# board.net
KiCad netlist of a schematic drawn in EAGLE
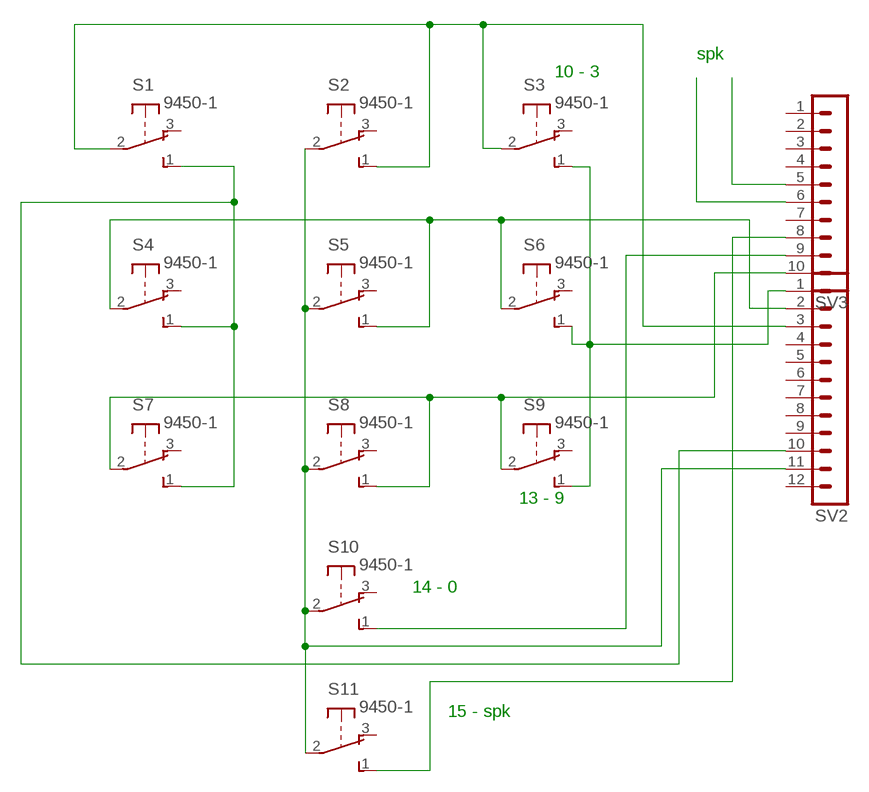
[diagram p0: schematic, sheet 1]

(export (version "E")
  (design (tool "Eeschema 10.0.6"))
  (components
    (comp (ref "S1")
      (value "9450-1")
      (footprint "eagle-import:9450-1")
      (libsource (lib "eagle-import") (part "9450-1"))
    )
    (comp (ref "S2")
      (value "9450-1")
      (footprint "eagle-import:9450-1")
      (libsource (lib "eagle-import") (part "9450-1"))
    )
    (comp (ref "S3")
      (value "9450-1")
      (footprint "eagle-import:9450-1")
      (libsource (lib "eagle-import") (part "9450-1"))
    )
    (comp (ref "S4")
      (value "9450-1")
      (footprint "eagle-import:9450-1")
      (libsource (lib "eagle-import") (part "9450-1"))
    )
    (comp (ref "S5")
      (value "9450-1")
      (footprint "eagle-import:9450-1")
      (libsource (lib "eagle-import") (part "9450-1"))
    )
    (comp (ref "S6")
      (value "9450-1")
      (footprint "eagle-import:9450-1")
      (libsource (lib "eagle-import") (part "9450-1"))
    )
    (comp (ref "S7")
      (value "9450-1")
      (footprint "eagle-import:9450-1")
      (libsource (lib "eagle-import") (part "9450-1"))
    )
    (comp (ref "S8")
      (value "9450-1")
      (footprint "eagle-import:9450-1")
      (libsource (lib "eagle-import") (part "9450-1"))
    )
    (comp (ref "S9")
      (value "9450-1")
      (footprint "eagle-import:9450-1")
      (libsource (lib "eagle-import") (part "9450-1"))
    )
    (comp (ref "S10")
      (value "9450-1")
      (footprint "eagle-import:9450-1")
      (libsource (lib "eagle-import") (part "9450-1"))
    )
    (comp (ref "S11")
      (value "9450-1")
      (footprint "eagle-import:9450-1")
      (libsource (lib "eagle-import") (part "9450-1"))
    )
    (comp (ref "SV2")
      (value "MA12-1")
      (footprint "eagle-import:MA12-1")
      (libsource (lib "eagle-import") (part "MA12-1"))
    )
    (comp (ref "SV3")
      (value "MA10-1")
      (footprint "eagle-import:MA10-1")
      (libsource (lib "eagle-import") (part "MA10-1"))
    )
  )
  (nets
    (net (code "1") (name "Net-(S1-P)") (class "Default")
      (node (ref "S1") (pin "2") (pinfunction "P_2") (pintype "passive"))
      (node (ref "S2") (pin "1") (pinfunction "S_1") (pintype "passive"))
      (node (ref "S3") (pin "2") (pinfunction "P_2") (pintype "passive"))
      (node (ref "SV2") (pin "3") (pinfunction "3_3") (pintype "passive"))
    )
    (net (code "2") (name "Net-(S1-S)") (class "Default")
      (node (ref "S1") (pin "1") (pinfunction "S_1") (pintype "passive"))
      (node (ref "S4") (pin "1") (pinfunction "S_1") (pintype "passive"))
      (node (ref "S7") (pin "1") (pinfunction "S_1") (pintype "passive"))
      (node (ref "SV2") (pin "10") (pinfunction "10_10") (pintype "passive"))
    )
    (net (code "3") (name "Net-(S3-S)") (class "Default")
      (node (ref "S3") (pin "1") (pinfunction "S_1") (pintype "passive"))
      (node (ref "S6") (pin "1") (pinfunction "S_1") (pintype "passive"))
      (node (ref "S9") (pin "1") (pinfunction "S_1") (pintype "passive"))
      (node (ref "SV2") (pin "1") (pinfunction "1_1") (pintype "passive"))
    )
    (net (code "4") (name "Net-(S4-P)") (class "Default")
      (node (ref "S4") (pin "2") (pinfunction "P_2") (pintype "passive"))
      (node (ref "S5") (pin "1") (pinfunction "S_1") (pintype "passive"))
      (node (ref "S6") (pin "2") (pinfunction "P_2") (pintype "passive"))
      (node (ref "SV2") (pin "2") (pinfunction "2_2") (pintype "passive"))
    )
    (net (code "5") (name "Net-(S7-P)") (class "Default")
      (node (ref "S7") (pin "2") (pinfunction "P_2") (pintype "passive"))
      (node (ref "S8") (pin "1") (pinfunction "S_1") (pintype "passive"))
      (node (ref "S9") (pin "2") (pinfunction "P_2") (pintype "passive"))
      (node (ref "SV3") (pin "10") (pinfunction "10_10") (pintype "passive"))
    )
    (net (code "6") (name "Net-(S10-P)") (class "Default")
      (node (ref "S10") (pin "2") (pinfunction "P_2") (pintype "passive"))
      (node (ref "S11") (pin "2") (pinfunction "P_2") (pintype "passive"))
      (node (ref "S2") (pin "2") (pinfunction "P_2") (pintype "passive"))
      (node (ref "S5") (pin "2") (pinfunction "P_2") (pintype "passive"))
      (node (ref "S8") (pin "2") (pinfunction "P_2") (pintype "passive"))
      (node (ref "SV2") (pin "11") (pinfunction "11_11") (pintype "passive"))
    )
    (net (code "7") (name "Net-(S10-S)") (class "Default")
      (node (ref "S10") (pin "1") (pinfunction "S_1") (pintype "passive"))
      (node (ref "SV3") (pin "9") (pinfunction "9_9") (pintype "passive"))
    )
    (net (code "8") (name "Net-(S11-S)") (class "Default")
      (node (ref "S11") (pin "1") (pinfunction "S_1") (pintype "passive"))
      (node (ref "SV3") (pin "8") (pinfunction "8_8") (pintype "passive"))
    )
    (net (code "9") (name "unconnected-(S1-O-Pad3)") (class "Default")
      (node (ref "S1") (pin "3") (pinfunction "O_3") (pintype "passive"))
    )
    (net (code "10") (name "unconnected-(S2-O-Pad3)") (class "Default")
      (node (ref "S2") (pin "3") (pinfunction "O_3") (pintype "passive"))
    )
    (net (code "11") (name "unconnected-(S3-O-Pad3)") (class "Default")
      (node (ref "S3") (pin "3") (pinfunction "O_3") (pintype "passive"))
    )
    (net (code "12") (name "unconnected-(S4-O-Pad3)") (class "Default")
      (node (ref "S4") (pin "3") (pinfunction "O_3") (pintype "passive"))
    )
    (net (code "13") (name "unconnected-(S5-O-Pad3)") (class "Default")
      (node (ref "S5") (pin "3") (pinfunction "O_3") (pintype "passive"))
    )
    (net (code "14") (name "unconnected-(S6-O-Pad3)") (class "Default")
      (node (ref "S6") (pin "3") (pinfunction "O_3") (pintype "passive"))
    )
    (net (code "15") (name "unconnected-(S7-O-Pad3)") (class "Default")
      (node (ref "S7") (pin "3") (pinfunction "O_3") (pintype "passive"))
    )
    (net (code "16") (name "unconnected-(S8-O-Pad3)") (class "Default")
      (node (ref "S8") (pin "3") (pinfunction "O_3") (pintype "passive"))
    )
    (net (code "17") (name "unconnected-(S9-O-Pad3)") (class "Default")
      (node (ref "S9") (pin "3") (pinfunction "O_3") (pintype "passive"))
    )
    (net (code "18") (name "unconnected-(S10-O-Pad3)") (class "Default")
      (node (ref "S10") (pin "3") (pinfunction "O_3") (pintype "passive"))
    )
    (net (code "19") (name "unconnected-(S11-O-Pad3)") (class "Default")
      (node (ref "S11") (pin "3") (pinfunction "O_3") (pintype "passive"))
    )
    (net (code "20") (name "unconnected-(SV2-Pad4)") (class "Default")
      (node (ref "SV2") (pin "4") (pinfunction "4_4") (pintype "passive"))
    )
    (net (code "21") (name "unconnected-(SV2-Pad5)") (class "Default")
      (node (ref "SV2") (pin "5") (pinfunction "5_5") (pintype "passive"))
    )
    (net (code "22") (name "unconnected-(SV2-Pad6)") (class "Default")
      (node (ref "SV2") (pin "6") (pinfunction "6_6") (pintype "passive"))
    )
    (net (code "23") (name "unconnected-(SV2-Pad7)") (class "Default")
      (node (ref "SV2") (pin "7") (pinfunction "7_7") (pintype "passive"))
    )
    (net (code "24") (name "unconnected-(SV2-Pad8)") (class "Default")
      (node (ref "SV2") (pin "8") (pinfunction "8_8") (pintype "passive"))
    )
    (net (code "25") (name "unconnected-(SV2-Pad9)") (class "Default")
      (node (ref "SV2") (pin "9") (pinfunction "9_9") (pintype "passive"))
    )
    (net (code "26") (name "unconnected-(SV2-Pad12)") (class "Default")
      (node (ref "SV2") (pin "12") (pinfunction "12_12") (pintype "passive"))
    )
    (net (code "27") (name "unconnected-(SV3-Pad1)") (class "Default")
      (node (ref "SV3") (pin "1") (pinfunction "1_1") (pintype "passive"))
    )
    (net (code "28") (name "unconnected-(SV3-Pad2)") (class "Default")
      (node (ref "SV3") (pin "2") (pinfunction "2_2") (pintype "passive"))
    )
    (net (code "29") (name "unconnected-(SV3-Pad3)") (class "Default")
      (node (ref "SV3") (pin "3") (pinfunction "3_3") (pintype "passive"))
    )
    (net (code "30") (name "unconnected-(SV3-Pad4)") (class "Default")
      (node (ref "SV3") (pin "4") (pinfunction "4_4") (pintype "passive"))
    )
    (net (code "31") (name "unconnected-(SV3-Pad5)") (class "Default")
      (node (ref "SV3") (pin "5") (pinfunction "5_5") (pintype "passive"))
    )
    (net (code "32") (name "unconnected-(SV3-Pad6)") (class "Default")
      (node (ref "SV3") (pin "6") (pinfunction "6_6") (pintype "passive"))
    )
    (net (code "33") (name "unconnected-(SV3-Pad7)") (class "Default")
      (node (ref "SV3") (pin "7") (pinfunction "7_7") (pintype "passive"))
    )
  )
)
